# SparkGapSchematic.net
KiCad netlist of a schematic drawn in Altium Designer
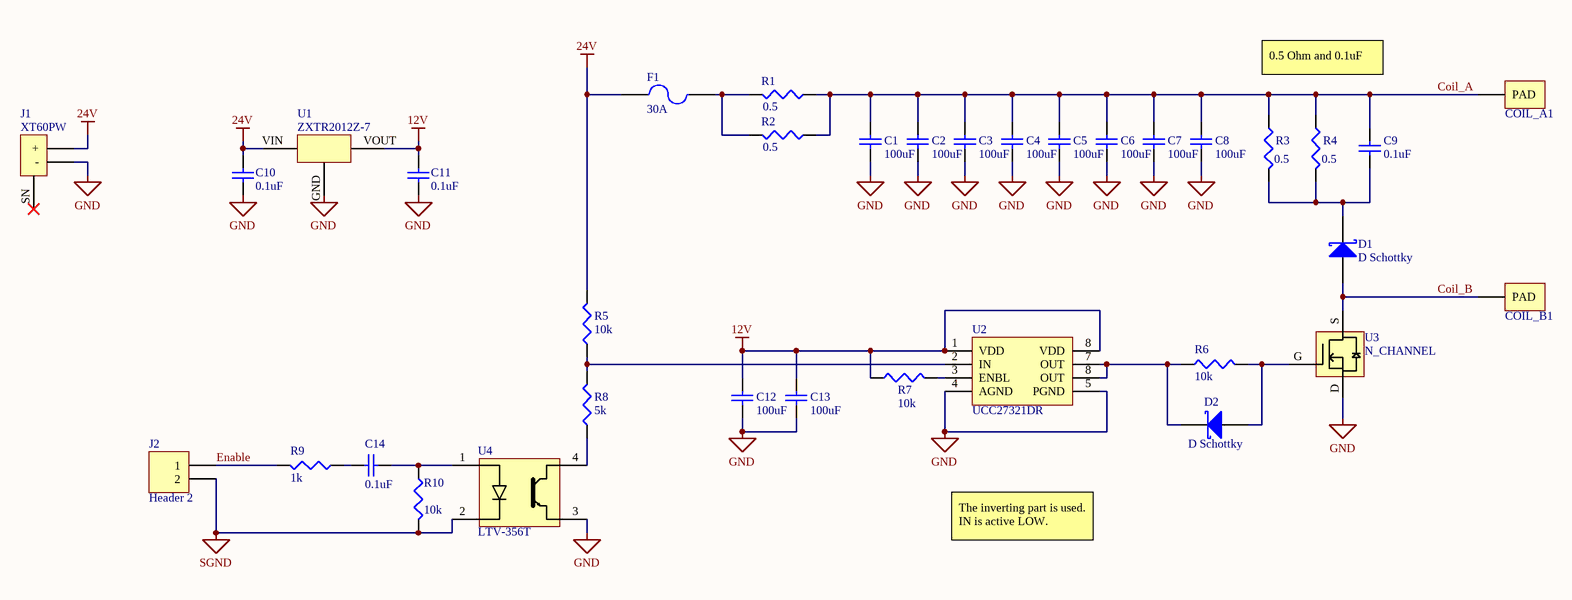
[diagram p0: SparkGapSchematic.SchDoc]

(export (version "E")
  (design (tool "Eeschema 10.0.6"))
  (components
    (comp (ref "C1")
      (value "100uF")
      (footprint "CAP_40mm")
      (description "Capacitor")
      (fields (field (name "Comment") "Cap") (field (name "PUBLISHER") "Altium Limited"))
      (libsource (lib "Miscellaneous Devices") (part "Cap"))
    )
    (comp (ref "C2")
      (value "100uF")
      (footprint "CAP_40mm")
      (description "Capacitor")
      (fields (field (name "Comment") "Cap") (field (name "PUBLISHER") "Altium Limited"))
      (libsource (lib "Miscellaneous Devices") (part "Cap"))
    )
    (comp (ref "C3")
      (value "100uF")
      (footprint "CAP_40mm")
      (description "Capacitor")
      (fields (field (name "Comment") "Cap") (field (name "PUBLISHER") "Altium Limited"))
      (libsource (lib "Miscellaneous Devices") (part "Cap"))
    )
    (comp (ref "C4")
      (value "100uF")
      (footprint "CAP_40mm")
      (description "Capacitor")
      (fields (field (name "Comment") "Cap") (field (name "PUBLISHER") "Altium Limited"))
      (libsource (lib "Miscellaneous Devices") (part "Cap"))
    )
    (comp (ref "C5")
      (value "100uF")
      (footprint "CAP_40mm")
      (description "Capacitor")
      (fields (field (name "Comment") "Cap") (field (name "PUBLISHER") "Altium Limited"))
      (libsource (lib "Miscellaneous Devices") (part "Cap"))
    )
    (comp (ref "C6")
      (value "100uF")
      (footprint "CAP_40mm")
      (description "Capacitor")
      (fields (field (name "Comment") "Cap") (field (name "PUBLISHER") "Altium Limited"))
      (libsource (lib "Miscellaneous Devices") (part "Cap"))
    )
    (comp (ref "C7")
      (value "100uF")
      (footprint "CAP_40mm")
      (description "Capacitor")
      (fields (field (name "Comment") "Cap") (field (name "PUBLISHER") "Altium Limited"))
      (libsource (lib "Miscellaneous Devices") (part "Cap"))
    )
    (comp (ref "C8")
      (value "100uF")
      (footprint "CAP_40mm")
      (description "Capacitor")
      (fields (field (name "Comment") "Cap") (field (name "PUBLISHER") "Altium Limited"))
      (libsource (lib "Miscellaneous Devices") (part "Cap"))
    )
    (comp (ref "C9")
      (value "0.1uF")
      (footprint "6-0805_L")
      (description "Capacitor")
      (fields (field (name "Comment") "Cap") (field (name "PUBLISHER") "Altium Limited"))
      (libsource (lib "Miscellaneous Devices") (part "Cap"))
    )
    (comp (ref "C10")
      (value "0.1uF")
      (footprint "6-0805_L")
      (description "Capacitor")
      (fields (field (name "Comment") "Cap") (field (name "PUBLISHER") "Altium Limited"))
      (libsource (lib "Miscellaneous Devices") (part "Cap"))
    )
    (comp (ref "C11")
      (value "0.1uF")
      (footprint "6-0805_L")
      (description "Capacitor")
      (fields (field (name "Comment") "Cap") (field (name "PUBLISHER") "Altium Limited"))
      (libsource (lib "Miscellaneous Devices") (part "Cap"))
    )
    (comp (ref "C12")
      (value "100uF")
      (footprint "6-0805_L")
      (description "Capacitor")
      (fields (field (name "Comment") "Cap") (field (name "PUBLISHER") "Altium Limited"))
      (libsource (lib "Miscellaneous Devices") (part "Cap"))
    )
    (comp (ref "C13")
      (value "100uF")
      (footprint "6-0805_L")
      (description "Capacitor")
      (fields (field (name "Comment") "Cap") (field (name "PUBLISHER") "Altium Limited"))
      (libsource (lib "Miscellaneous Devices") (part "Cap"))
    )
    (comp (ref "C14")
      (value "0.1uF")
      (footprint "6-0805_L")
      (description "Capacitor")
      (fields (field (name "Comment") "Cap") (field (name "PUBLISHER") "Altium Limited"))
      (libsource (lib "Miscellaneous Devices") (part "Cap"))
    )
    (comp (ref "COIL_A1")
      (value "PAD")
      (footprint "PAD")
      (libsource (lib "RS_Library_Schematic") (part "PAD"))
    )
    (comp (ref "COIL_B1")
      (value "PAD")
      (footprint "PAD")
      (libsource (lib "RS_Library_Schematic") (part "PAD"))
    )
    (comp (ref "D1")
      (value "D Schottky")
      (footprint "SMB")
      (description "Schottky Diode")
      (fields (field (name "PUBLISHER") "Altium Limited"))
      (libsource (lib "Miscellaneous Devices") (part "D Schottky"))
    )
    (comp (ref "D2")
      (value "D Schottky")
      (footprint "SOD123F")
      (description "Schottky Diode")
      (fields (field (name "PUBLISHER") "Altium Limited"))
      (libsource (lib "Miscellaneous Devices") (part "D Schottky"))
    )
    (comp (ref "F1")
      (value "30A")
      (footprint "FUSE_HOLDER")
      (description "Fuse")
      (fields (field (name "PUBLISHER") "Altium Limited"))
      (libsource (lib "Miscellaneous Devices") (part "Fuse 2"))
    )
    (comp (ref "J1")
      (value "XT60PW")
      (footprint "XT60PW")
      (libsource (lib "RS_Library_Schematic") (part "XT60PW"))
    )
    (comp (ref "J2")
      (value "Header 2")
      (footprint "HDR1X2")
      (description "Header, 2-Pin")
      (fields (field (name "PUBLISHER") "Altium Limited"))
      (libsource (lib "Miscellaneous Connectors") (part "Header 2"))
    )
    (comp (ref "R1")
      (value "0.5")
      (footprint "12Z-2010")
      (description "Resistor")
      (fields (field (name "Comment") "Res3") (field (name "PUBLISHER") "Altium Limited"))
      (libsource (lib "Miscellaneous Devices") (part "Res3"))
    )
    (comp (ref "R2")
      (value "0.5")
      (footprint "12Z-2010")
      (description "Resistor")
      (fields (field (name "Comment") "Res3") (field (name "PUBLISHER") "Altium Limited"))
      (libsource (lib "Miscellaneous Devices") (part "Res3"))
    )
    (comp (ref "R3")
      (value "0.5")
      (footprint "12Z-2010")
      (description "Resistor")
      (fields (field (name "Comment") "Res3") (field (name "PUBLISHER") "Altium Limited"))
      (libsource (lib "Miscellaneous Devices") (part "Res3"))
    )
    (comp (ref "R4")
      (value "0.5")
      (footprint "12Z-2010")
      (description "Resistor")
      (fields (field (name "Comment") "Res3") (field (name "PUBLISHER") "Altium Limited"))
      (libsource (lib "Miscellaneous Devices") (part "Res3"))
    )
    (comp (ref "R5")
      (value "10k")
      (footprint "6-0805_L")
      (description "Resistor")
      (fields (field (name "Comment") "Res3") (field (name "PUBLISHER") "Altium Limited"))
      (libsource (lib "Miscellaneous Devices") (part "Res3"))
    )
    (comp (ref "R6")
      (value "10k")
      (footprint "6-0805_L")
      (description "Resistor")
      (fields (field (name "Comment") "Res3") (field (name "PUBLISHER") "Altium Limited"))
      (libsource (lib "Miscellaneous Devices") (part "Res3"))
    )
    (comp (ref "R7")
      (value "10k")
      (footprint "6-0805_L")
      (description "Resistor")
      (fields (field (name "Comment") "Res3") (field (name "PUBLISHER") "Altium Limited"))
      (libsource (lib "Miscellaneous Devices") (part "Res3"))
    )
    (comp (ref "R8")
      (value "5k")
      (footprint "6-0805_L")
      (description "Resistor")
      (fields (field (name "Comment") "Res3") (field (name "PUBLISHER") "Altium Limited"))
      (libsource (lib "Miscellaneous Devices") (part "Res3"))
    )
    (comp (ref "R9")
      (value "1k")
      (footprint "6-0805_L")
      (description "Resistor")
      (fields (field (name "Comment") "Res3") (field (name "PUBLISHER") "Altium Limited"))
      (libsource (lib "Miscellaneous Devices") (part "Res3"))
    )
    (comp (ref "R10")
      (value "10k")
      (footprint "6-0805_L")
      (description "Resistor")
      (fields (field (name "PUBLISHER") "Altium Limited"))
      (libsource (lib "Miscellaneous Devices") (part "Res3"))
    )
    (comp (ref "U1")
      (value "ZXTR2012Z-7")
      (footprint "ZXTR2012Z")
      (libsource (lib "RS_Library_Schematic") (part "ZXTR2012Z-7"))
    )
    (comp (ref "U2")
      (value "UCC27321DR")
      (footprint "Gate_Driver_UCC27321DR")
      (libsource (lib "RS_Library_Schematic") (part "UCC27321DR"))
    )
    (comp (ref "U3")
      (value "N_CHANNEL")
      (footprint "N_CH_SUG90090E")
      (libsource (lib "RS_Library_Schematic") (part "N_CHANNEL"))
    )
    (comp (ref "U4")
      (value "LTV-356T")
      (footprint "OptoIsolator_LTV-356T-B")
      (libsource (lib "RS_Library_Schematic") (part "LTV-356T"))
    )
  )
  (nets
    (net (code "1") (name "/Coil_A") (class "Default")
      (node (ref "C1") (pin "2") (pinfunction "2_2") (pintype "passive"))
      (node (ref "C2") (pin "2") (pinfunction "2_2") (pintype "passive"))
      (node (ref "C3") (pin "2") (pinfunction "2_2") (pintype "passive"))
      (node (ref "C4") (pin "2") (pinfunction "2_2") (pintype "passive"))
      (node (ref "C5") (pin "2") (pinfunction "2_2") (pintype "passive"))
      (node (ref "C6") (pin "2") (pinfunction "2_2") (pintype "passive"))
      (node (ref "C7") (pin "2") (pinfunction "2_2") (pintype "passive"))
      (node (ref "C8") (pin "2") (pinfunction "2_2") (pintype "passive"))
      (node (ref "C9") (pin "2") (pinfunction "2_2") (pintype "passive"))
      (node (ref "COIL_A1") (pin "PAD") (pinfunction "PAD_PAD") (pintype "passive"))
      (node (ref "R1") (pin "1") (pinfunction "1_1") (pintype "passive"))
      (node (ref "R2") (pin "1") (pinfunction "1_1") (pintype "passive"))
      (node (ref "R3") (pin "1") (pinfunction "1_1") (pintype "passive"))
      (node (ref "R4") (pin "1") (pinfunction "1_1") (pintype "passive"))
    )
    (net (code "2") (name "/Coil_B") (class "Default")
      (node (ref "COIL_B1") (pin "PAD") (pinfunction "PAD_PAD") (pintype "passive"))
      (node (ref "D1") (pin "1") (pinfunction "A_1") (pintype "passive"))
      (node (ref "U3") (pin "S") (pinfunction "S_S") (pintype "passive"))
    )
    (net (code "3") (name "/Enable") (class "Default")
      (node (ref "J2") (pin "1") (pinfunction "1_1") (pintype "passive"))
      (node (ref "R9") (pin "2") (pinfunction "2_2") (pintype "passive"))
    )
    (net (code "4") (name "12V") (class "Default")
      (node (ref "C11") (pin "2") (pinfunction "2_2") (pintype "passive"))
      (node (ref "C12") (pin "2") (pinfunction "2_2") (pintype "passive"))
      (node (ref "C13") (pin "2") (pinfunction "2_2") (pintype "passive"))
      (node (ref "R7") (pin "1") (pinfunction "1_1") (pintype "passive"))
      (node (ref "U1") (pin "VOUT") (pinfunction "VOUT_VOUT") (pintype "passive"))
      (node (ref "U2") (pin "1") (pinfunction "VDD_1") (pintype "passive"))
      (node (ref "U2") (pin "8") (pinfunction "VDD_8") (pintype "passive"))
    )
    (net (code "5") (name "24V") (class "Default")
      (node (ref "C10") (pin "2") (pinfunction "2_2") (pintype "passive"))
      (node (ref "F1") (pin "1") (pinfunction "1_1") (pintype "passive"))
      (node (ref "J1") (pin "+") (pinfunction "+_+") (pintype "passive"))
      (node (ref "R5") (pin "2") (pinfunction "2_2") (pintype "passive"))
      (node (ref "U1") (pin "VIN") (pinfunction "VIN_VIN") (pintype "passive"))
    )
    (net (code "6") (name "GND") (class "Default")
      (node (ref "C1") (pin "1") (pinfunction "1_1") (pintype "passive"))
      (node (ref "C10") (pin "1") (pinfunction "1_1") (pintype "passive"))
      (node (ref "C11") (pin "1") (pinfunction "1_1") (pintype "passive"))
      (node (ref "C12") (pin "1") (pinfunction "1_1") (pintype "passive"))
      (node (ref "C13") (pin "1") (pinfunction "1_1") (pintype "passive"))
      (node (ref "C2") (pin "1") (pinfunction "1_1") (pintype "passive"))
      (node (ref "C3") (pin "1") (pinfunction "1_1") (pintype "passive"))
      (node (ref "C4") (pin "1") (pinfunction "1_1") (pintype "passive"))
      (node (ref "C5") (pin "1") (pinfunction "1_1") (pintype "passive"))
      (node (ref "C6") (pin "1") (pinfunction "1_1") (pintype "passive"))
      (node (ref "C7") (pin "1") (pinfunction "1_1") (pintype "passive"))
      (node (ref "C8") (pin "1") (pinfunction "1_1") (pintype "passive"))
      (node (ref "J1") (pin "-") (pinfunction "-_-") (pintype "passive"))
      (node (ref "U1") (pin "GND") (pinfunction "GND_GND") (pintype "passive"))
      (node (ref "U2") (pin "4") (pinfunction "AGND_4") (pintype "passive"))
      (node (ref "U2") (pin "5") (pinfunction "PGND_5") (pintype "passive"))
      (node (ref "U3") (pin "D") (pinfunction "D_D") (pintype "passive"))
      (node (ref "U4") (pin "3") (pinfunction "Emmiter_3") (pintype "passive"))
    )
    (net (code "7") (name "Net-(C14-Pad2)") (class "Default")
      (node (ref "C14") (pin "2") (pinfunction "2_2") (pintype "passive"))
      (node (ref "R9") (pin "1") (pinfunction "1_1") (pintype "passive"))
    )
    (net (code "8") (name "Net-(D1-K)") (class "Default")
      (node (ref "C9") (pin "1") (pinfunction "1_1") (pintype "passive"))
      (node (ref "D1") (pin "2") (pinfunction "K_2") (pintype "passive"))
      (node (ref "R3") (pin "2") (pinfunction "2_2") (pintype "passive"))
      (node (ref "R4") (pin "2") (pinfunction "2_2") (pintype "passive"))
    )
    (net (code "9") (name "Net-(D2-A)") (class "Default")
      (node (ref "D2") (pin "1") (pinfunction "A_1") (pintype "passive"))
      (node (ref "R6") (pin "2") (pinfunction "2_2") (pintype "passive"))
      (node (ref "U3") (pin "G") (pinfunction "G_G") (pintype "passive"))
    )
    (net (code "10") (name "Net-(D2-K)") (class "Default")
      (node (ref "D2") (pin "2") (pinfunction "K_2") (pintype "passive"))
      (node (ref "R6") (pin "1") (pinfunction "1_1") (pintype "passive"))
      (node (ref "U2") (pin "7") (pinfunction "OUT_7") (pintype "passive"))
      (node (ref "U2") (pin "8") (pinfunction "OUT_8") (pintype "passive"))
    )
    (net (code "11") (name "Net-(F1-Pad2)") (class "Default")
      (node (ref "F1") (pin "2") (pinfunction "2_2") (pintype "passive"))
      (node (ref "R1") (pin "2") (pinfunction "2_2") (pintype "passive"))
      (node (ref "R2") (pin "2") (pinfunction "2_2") (pintype "passive"))
    )
    (net (code "12") (name "Net-(U2-ENBL)") (class "Default")
      (node (ref "R7") (pin "2") (pinfunction "2_2") (pintype "passive"))
      (node (ref "U2") (pin "3") (pinfunction "ENBL_3") (pintype "passive"))
    )
    (net (code "13") (name "Net-(U2-IN)") (class "Default")
      (node (ref "R5") (pin "1") (pinfunction "1_1") (pintype "passive"))
      (node (ref "R8") (pin "2") (pinfunction "2_2") (pintype "passive"))
      (node (ref "U2") (pin "2") (pinfunction "IN_2") (pintype "passive"))
    )
    (net (code "14") (name "Net-(U4-Anode)") (class "Default")
      (node (ref "C14") (pin "1") (pinfunction "1_1") (pintype "passive"))
      (node (ref "R10") (pin "1") (pinfunction "1_1") (pintype "passive"))
      (node (ref "U4") (pin "1") (pinfunction "Anode_1") (pintype "passive"))
    )
    (net (code "15") (name "Net-(U4-Collector)") (class "Default")
      (node (ref "R8") (pin "1") (pinfunction "1_1") (pintype "passive"))
      (node (ref "U4") (pin "4") (pinfunction "Collector_4") (pintype "passive"))
    )
    (net (code "16") (name "SGND") (class "Default")
      (node (ref "J2") (pin "2") (pinfunction "2_2") (pintype "passive"))
      (node (ref "R10") (pin "2") (pinfunction "2_2") (pintype "passive"))
      (node (ref "U4") (pin "2") (pinfunction "Cathode_2") (pintype "passive"))
    )
    (net (code "17") (name "unconnected-(J1-PadSN)") (class "Default")
      (node (ref "J1") (pin "SN") (pinfunction "SN_SN") (pintype "passive+no_connect"))
    )
  )
)
